# ToF_sensors.net
KiCad netlist of a schematic drawn in Altium Designer
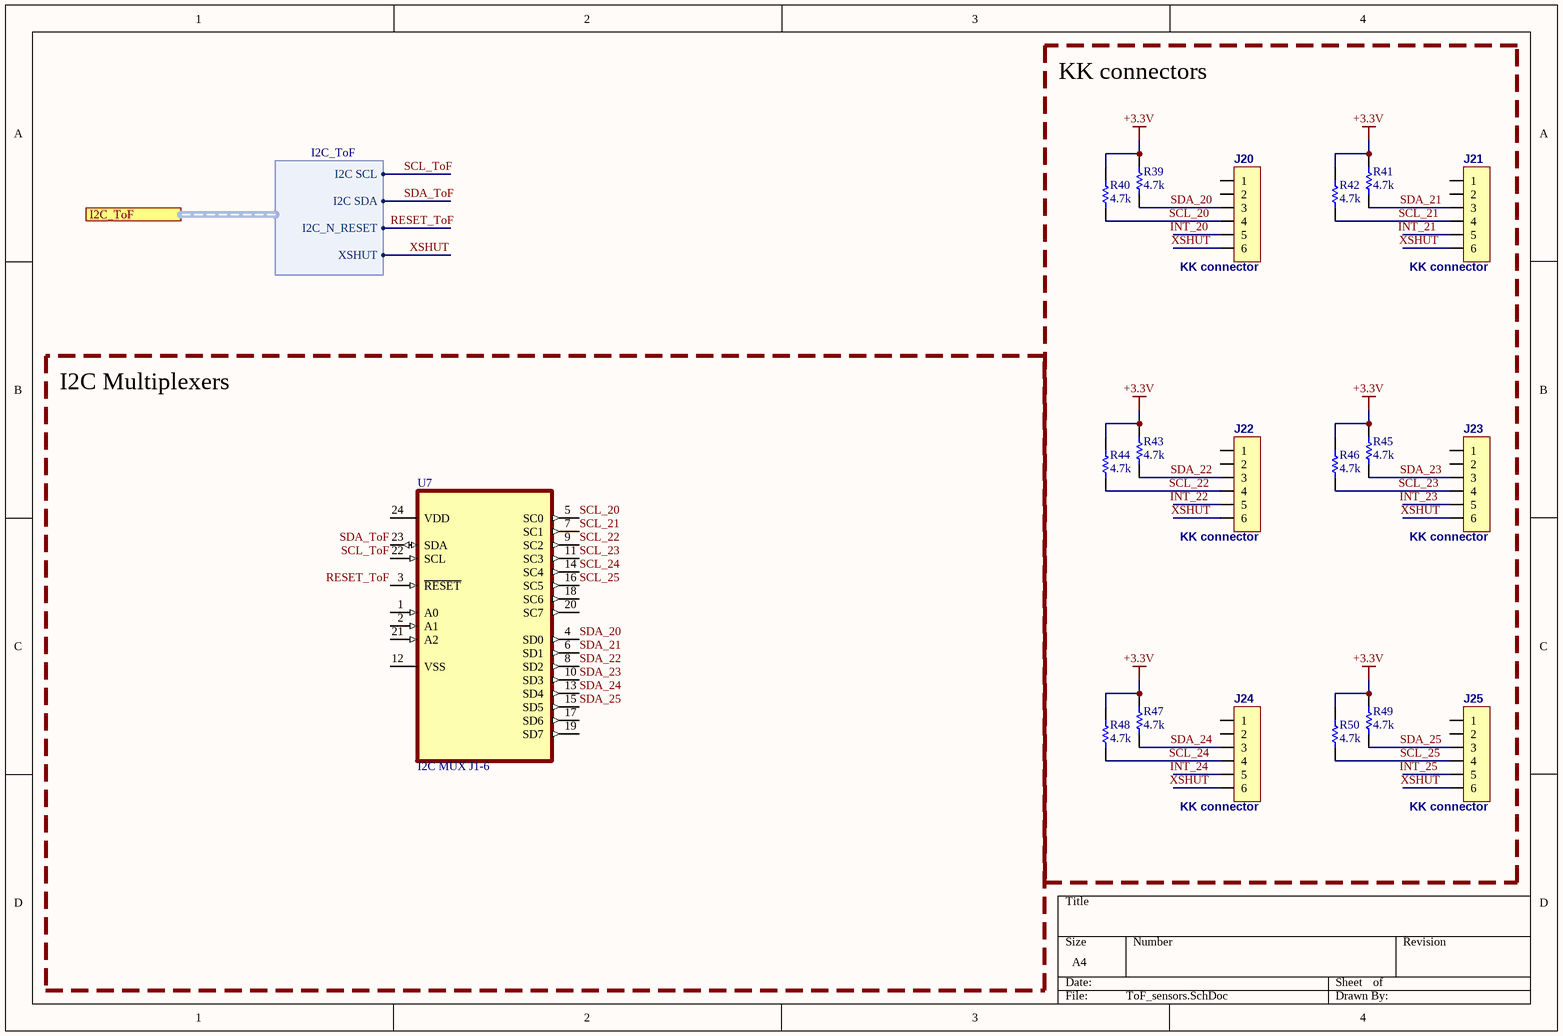
[diagram p0: ToF_sensors.SchDoc]

(export (version "E")
  (design (tool "Eeschema 10.0.6"))
  (components
    (comp (ref "J20")
      (value "KK connector")
      (footprint "KK/2.54/6")
      (description "Connector: PCB-cable; KK; socket; male; PIN:6; straight/right-angle; tinned; THT, KK/2,54mm")
      (libsource (lib "kk") (part "CN_6x1"))
    )
    (comp (ref "J21")
      (value "KK connector")
      (footprint "KK/2.54/6")
      (description "Connector: PCB-cable; KK; socket; male; PIN:6; straight/right-angle; tinned; THT, KK/2,54mm")
      (libsource (lib "kk") (part "CN_6x1"))
    )
    (comp (ref "J22")
      (value "KK connector")
      (footprint "KK/2.54/6")
      (description "Connector: PCB-cable; KK; socket; male; PIN:6; straight/right-angle; tinned; THT, KK/2,54mm")
      (libsource (lib "kk") (part "CN_6x1"))
    )
    (comp (ref "J23")
      (value "KK connector")
      (footprint "KK/2.54/6")
      (description "Connector: PCB-cable; KK; socket; male; PIN:6; straight/right-angle; tinned; THT, KK/2,54mm")
      (libsource (lib "kk") (part "CN_6x1"))
    )
    (comp (ref "J24")
      (value "KK connector")
      (footprint "KK/2.54/6")
      (description "Connector: PCB-cable; KK; socket; male; PIN:6; straight/right-angle; tinned; THT, KK/2,54mm")
      (libsource (lib "kk") (part "CN_6x1"))
    )
    (comp (ref "J25")
      (value "KK connector")
      (footprint "KK/2.54/6")
      (description "Connector: PCB-cable; KK; socket; male; PIN:6; straight/right-angle; tinned; THT, KK/2,54mm")
      (libsource (lib "kk") (part "CN_6x1"))
    )
    (comp (ref "R39")
      (value "4.7k")
      (footprint "RESC1609X50X30ML10T20")
      (description "RES 4,7K OHM 1% 0,1W 0603 RNCS0603BKE10K0")
      (fields (field (name "PART NUMBER") "CRCW060311K0FKEA") (field (name "MANUFACTURER") "Vishay Dale"))
      (libsource (lib "Altium Content Vault") (part "RES"))
    )
    (comp (ref "R40")
      (value "4.7k")
      (footprint "RESC1609X50X30ML10T20")
      (description "RES 4,7K OHM 1% 0,1W 0603 RNCS0603BKE10K0")
      (fields (field (name "PART NUMBER") "CRCW060311K0FKEA") (field (name "MANUFACTURER") "Vishay Dale"))
      (libsource (lib "Altium Content Vault") (part "RES"))
    )
    (comp (ref "R41")
      (value "4.7k")
      (footprint "RESC1609X50X30ML10T20")
      (description "RES 4,7K OHM 1% 0,1W 0603 RNCS0603BKE10K0")
      (fields (field (name "PART NUMBER") "CRCW060311K0FKEA") (field (name "MANUFACTURER") "Vishay Dale"))
      (libsource (lib "Altium Content Vault") (part "RES"))
    )
    (comp (ref "R42")
      (value "4.7k")
      (footprint "RESC1609X50X30ML10T20")
      (description "RES 4,7K OHM 1% 0,1W 0603 RNCS0603BKE10K0")
      (fields (field (name "PART NUMBER") "CRCW060311K0FKEA") (field (name "MANUFACTURER") "Vishay Dale"))
      (libsource (lib "Altium Content Vault") (part "RES"))
    )
    (comp (ref "R43")
      (value "4.7k")
      (footprint "RESC1609X50X30ML10T20")
      (description "RES 4,7K OHM 1% 0,1W 0603 RNCS0603BKE10K0")
      (fields (field (name "PART NUMBER") "CRCW060311K0FKEA") (field (name "MANUFACTURER") "Vishay Dale"))
      (libsource (lib "Altium Content Vault") (part "RES"))
    )
    (comp (ref "R44")
      (value "4.7k")
      (footprint "RESC1609X50X30ML10T20")
      (description "RES 4,7K OHM 1% 0,1W 0603 RNCS0603BKE10K0")
      (fields (field (name "PART NUMBER") "CRCW060311K0FKEA") (field (name "MANUFACTURER") "Vishay Dale"))
      (libsource (lib "Altium Content Vault") (part "RES"))
    )
    (comp (ref "R45")
      (value "4.7k")
      (footprint "RESC1609X50X30ML10T20")
      (description "RES 4,7K OHM 1% 0,1W 0603 RNCS0603BKE10K0")
      (fields (field (name "PART NUMBER") "CRCW060311K0FKEA") (field (name "MANUFACTURER") "Vishay Dale"))
      (libsource (lib "Altium Content Vault") (part "RES"))
    )
    (comp (ref "R46")
      (value "4.7k")
      (footprint "RESC1609X50X30ML10T20")
      (description "RES 4,7K OHM 1% 0,1W 0603 RNCS0603BKE10K0")
      (fields (field (name "PART NUMBER") "CRCW060311K0FKEA") (field (name "MANUFACTURER") "Vishay Dale"))
      (libsource (lib "Altium Content Vault") (part "RES"))
    )
    (comp (ref "R47")
      (value "4.7k")
      (footprint "RESC1609X50X30ML10T20")
      (description "RES 4,7K OHM 1% 0,1W 0603 RNCS0603BKE10K0")
      (fields (field (name "PART NUMBER") "CRCW060311K0FKEA") (field (name "MANUFACTURER") "Vishay Dale"))
      (libsource (lib "Altium Content Vault") (part "RES"))
    )
    (comp (ref "R48")
      (value "4.7k")
      (footprint "RESC1609X50X30ML10T20")
      (description "RES 4,7K OHM 1% 0,1W 0603 RNCS0603BKE10K0")
      (fields (field (name "PART NUMBER") "CRCW060311K0FKEA") (field (name "MANUFACTURER") "Vishay Dale"))
      (libsource (lib "Altium Content Vault") (part "RES"))
    )
    (comp (ref "R49")
      (value "4.7k")
      (footprint "RESC1609X50X30ML10T20")
      (description "RES 4,7K OHM 1% 0,1W 0603 RNCS0603BKE10K0")
      (fields (field (name "PART NUMBER") "CRCW060311K0FKEA") (field (name "MANUFACTURER") "Vishay Dale"))
      (libsource (lib "Altium Content Vault") (part "RES"))
    )
    (comp (ref "R50")
      (value "4.7k")
      (footprint "RESC1609X50X30ML10T20")
      (description "RES 4,7K OHM 1% 0,1W 0603 RNCS0603BKE10K0")
      (fields (field (name "PART NUMBER") "CRCW060311K0FKEA") (field (name "MANUFACTURER") "Vishay Dale"))
      (libsource (lib "Altium Content Vault") (part "RES"))
    )
    (comp (ref "U7")
      (value "I2C MUX J1-6")
      (footprint "SOP65P640X110-24N")
      (description "Translating Multiplexer Interface 24-TSSOP PCA9547PW,118")
      (fields (field (name "MP") "PCA9547PW,118") (field (name "MF") "NXP USA"))
      (libsource (lib "MyWorkspace") (part "PCA9547PW,118"))
    )
  )
  (nets
    (net (code "2") (name "+3.3V") (class "Default")
      (node (ref "R39") (pin "2") (pinfunction "2_2") (pintype "passive"))
      (node (ref "R40") (pin "2") (pinfunction "2_2") (pintype "passive"))
      (node (ref "R41") (pin "2") (pinfunction "2_2") (pintype "passive"))
      (node (ref "R42") (pin "2") (pinfunction "2_2") (pintype "passive"))
      (node (ref "R43") (pin "2") (pinfunction "2_2") (pintype "passive"))
      (node (ref "R44") (pin "2") (pinfunction "2_2") (pintype "passive"))
      (node (ref "R45") (pin "2") (pinfunction "2_2") (pintype "passive"))
      (node (ref "R46") (pin "2") (pinfunction "2_2") (pintype "passive"))
      (node (ref "R47") (pin "2") (pinfunction "2_2") (pintype "passive"))
      (node (ref "R48") (pin "2") (pinfunction "2_2") (pintype "passive"))
      (node (ref "R49") (pin "2") (pinfunction "2_2") (pintype "passive"))
      (node (ref "R50") (pin "2") (pinfunction "2_2") (pintype "passive"))
    )
    (net (code "3") (name "/INT_20") (class "Default")
      (node (ref "J20") (pin "5") (pinfunction "5_5") (pintype "passive"))
    )
    (net (code "4") (name "/INT_21") (class "Default")
      (node (ref "J21") (pin "5") (pinfunction "5_5") (pintype "passive"))
    )
    (net (code "5") (name "/INT_22") (class "Default")
      (node (ref "J22") (pin "5") (pinfunction "5_5") (pintype "passive"))
    )
    (net (code "6") (name "/INT_23") (class "Default")
      (node (ref "J23") (pin "5") (pinfunction "5_5") (pintype "passive"))
    )
    (net (code "7") (name "/INT_24") (class "Default")
      (node (ref "J24") (pin "5") (pinfunction "5_5") (pintype "passive"))
    )
    (net (code "8") (name "/INT_25") (class "Default")
      (node (ref "J25") (pin "5") (pinfunction "5_5") (pintype "passive"))
    )
    (net (code "9") (name "/RESET_ToF") (class "Default")
      (node (ref "U7") (pin "3") (pinfunction "~{RESET}_3") (pintype "input"))
    )
    (net (code "10") (name "/SCL_20") (class "Default")
      (node (ref "J20") (pin "4") (pinfunction "4_4") (pintype "passive"))
      (node (ref "R40") (pin "1") (pinfunction "1_1") (pintype "passive"))
      (node (ref "U7") (pin "5") (pinfunction "SC0_5") (pintype "output"))
    )
    (net (code "11") (name "/SCL_21") (class "Default")
      (node (ref "J21") (pin "4") (pinfunction "4_4") (pintype "passive"))
      (node (ref "R42") (pin "1") (pinfunction "1_1") (pintype "passive"))
      (node (ref "U7") (pin "7") (pinfunction "SC1_7") (pintype "output"))
    )
    (net (code "12") (name "/SCL_22") (class "Default")
      (node (ref "J22") (pin "4") (pinfunction "4_4") (pintype "passive"))
      (node (ref "R44") (pin "1") (pinfunction "1_1") (pintype "passive"))
      (node (ref "U7") (pin "9") (pinfunction "SC2_9") (pintype "output"))
    )
    (net (code "13") (name "/SCL_23") (class "Default")
      (node (ref "J23") (pin "4") (pinfunction "4_4") (pintype "passive"))
      (node (ref "R46") (pin "1") (pinfunction "1_1") (pintype "passive"))
      (node (ref "U7") (pin "11") (pinfunction "SC3_11") (pintype "output"))
    )
    (net (code "14") (name "/SCL_24") (class "Default")
      (node (ref "J24") (pin "4") (pinfunction "4_4") (pintype "passive"))
      (node (ref "R48") (pin "1") (pinfunction "1_1") (pintype "passive"))
      (node (ref "U7") (pin "14") (pinfunction "SC4_14") (pintype "output"))
    )
    (net (code "15") (name "/SCL_25") (class "Default")
      (node (ref "J25") (pin "4") (pinfunction "4_4") (pintype "passive"))
      (node (ref "R50") (pin "1") (pinfunction "1_1") (pintype "passive"))
      (node (ref "U7") (pin "16") (pinfunction "SC5_16") (pintype "output"))
    )
    (net (code "16") (name "/SCL_ToF") (class "Default")
      (node (ref "U7") (pin "22") (pinfunction "SCL_22") (pintype "input"))
    )
    (net (code "17") (name "/SDA_20") (class "Default")
      (node (ref "J20") (pin "3") (pinfunction "3_3") (pintype "passive"))
      (node (ref "R39") (pin "1") (pinfunction "1_1") (pintype "passive"))
      (node (ref "U7") (pin "4") (pinfunction "SD0_4") (pintype "output"))
    )
    (net (code "18") (name "/SDA_21") (class "Default")
      (node (ref "J21") (pin "3") (pinfunction "3_3") (pintype "passive"))
      (node (ref "R41") (pin "1") (pinfunction "1_1") (pintype "passive"))
      (node (ref "U7") (pin "6") (pinfunction "SD1_6") (pintype "output"))
    )
    (net (code "19") (name "/SDA_22") (class "Default")
      (node (ref "J22") (pin "3") (pinfunction "3_3") (pintype "passive"))
      (node (ref "R43") (pin "1") (pinfunction "1_1") (pintype "passive"))
      (node (ref "U7") (pin "8") (pinfunction "SD2_8") (pintype "output"))
    )
    (net (code "20") (name "/SDA_23") (class "Default")
      (node (ref "J23") (pin "3") (pinfunction "3_3") (pintype "passive"))
      (node (ref "R45") (pin "1") (pinfunction "1_1") (pintype "passive"))
      (node (ref "U7") (pin "10") (pinfunction "SD3_10") (pintype "output"))
    )
    (net (code "21") (name "/SDA_24") (class "Default")
      (node (ref "J24") (pin "3") (pinfunction "3_3") (pintype "passive"))
      (node (ref "R47") (pin "1") (pinfunction "1_1") (pintype "passive"))
      (node (ref "U7") (pin "13") (pinfunction "SD4_13") (pintype "output"))
    )
    (net (code "22") (name "/SDA_25") (class "Default")
      (node (ref "J25") (pin "3") (pinfunction "3_3") (pintype "passive"))
      (node (ref "R49") (pin "1") (pinfunction "1_1") (pintype "passive"))
      (node (ref "U7") (pin "15") (pinfunction "SD5_15") (pintype "output"))
    )
    (net (code "23") (name "/SDA_ToF") (class "Default")
      (node (ref "U7") (pin "23") (pinfunction "SDA_23") (pintype "bidirectional"))
    )
    (net (code "24") (name "/XSHUT") (class "Default")
      (node (ref "J20") (pin "6") (pinfunction "6_6") (pintype "passive"))
      (node (ref "J21") (pin "6") (pinfunction "6_6") (pintype "passive"))
      (node (ref "J22") (pin "6") (pinfunction "6_6") (pintype "passive"))
      (node (ref "J23") (pin "6") (pinfunction "6_6") (pintype "passive"))
      (node (ref "J24") (pin "6") (pinfunction "6_6") (pintype "passive"))
      (node (ref "J25") (pin "6") (pinfunction "6_6") (pintype "passive"))
    )
    (net (code "26") (name "unconnected-(J20-Pad1)") (class "Default")
      (node (ref "J20") (pin "1") (pinfunction "1_1") (pintype "passive"))
    )
    (net (code "27") (name "unconnected-(J20-Pad2)") (class "Default")
      (node (ref "J20") (pin "2") (pinfunction "2_2") (pintype "passive"))
    )
    (net (code "28") (name "unconnected-(J21-Pad1)") (class "Default")
      (node (ref "J21") (pin "1") (pinfunction "1_1") (pintype "passive"))
    )
    (net (code "29") (name "unconnected-(J21-Pad2)") (class "Default")
      (node (ref "J21") (pin "2") (pinfunction "2_2") (pintype "passive"))
    )
    (net (code "30") (name "unconnected-(J22-Pad1)") (class "Default")
      (node (ref "J22") (pin "1") (pinfunction "1_1") (pintype "passive"))
    )
    (net (code "31") (name "unconnected-(J22-Pad2)") (class "Default")
      (node (ref "J22") (pin "2") (pinfunction "2_2") (pintype "passive"))
    )
    (net (code "32") (name "unconnected-(J23-Pad1)") (class "Default")
      (node (ref "J23") (pin "1") (pinfunction "1_1") (pintype "passive"))
    )
    (net (code "33") (name "unconnected-(J23-Pad2)") (class "Default")
      (node (ref "J23") (pin "2") (pinfunction "2_2") (pintype "passive"))
    )
    (net (code "34") (name "unconnected-(J24-Pad1)") (class "Default")
      (node (ref "J24") (pin "1") (pinfunction "1_1") (pintype "passive"))
    )
    (net (code "35") (name "unconnected-(J24-Pad2)") (class "Default")
      (node (ref "J24") (pin "2") (pinfunction "2_2") (pintype "passive"))
    )
    (net (code "36") (name "unconnected-(J25-Pad1)") (class "Default")
      (node (ref "J25") (pin "1") (pinfunction "1_1") (pintype "passive"))
    )
    (net (code "37") (name "unconnected-(J25-Pad2)") (class "Default")
      (node (ref "J25") (pin "2") (pinfunction "2_2") (pintype "passive"))
    )
    (net (code "38") (name "unconnected-(U7-A0-Pad1)") (class "Default")
      (node (ref "U7") (pin "1") (pinfunction "A0_1") (pintype "input"))
    )
    (net (code "39") (name "unconnected-(U7-A1-Pad2)") (class "Default")
      (node (ref "U7") (pin "2") (pinfunction "A1_2") (pintype "input"))
    )
    (net (code "40") (name "unconnected-(U7-A2-Pad21)") (class "Default")
      (node (ref "U7") (pin "21") (pinfunction "A2_21") (pintype "input"))
    )
    (net (code "41") (name "unconnected-(U7-SC6-Pad18)") (class "Default")
      (node (ref "U7") (pin "18") (pinfunction "SC6_18") (pintype "output"))
    )
    (net (code "42") (name "unconnected-(U7-SC7-Pad20)") (class "Default")
      (node (ref "U7") (pin "20") (pinfunction "SC7_20") (pintype "output"))
    )
    (net (code "43") (name "unconnected-(U7-SD6-Pad17)") (class "Default")
      (node (ref "U7") (pin "17") (pinfunction "SD6_17") (pintype "output"))
    )
    (net (code "44") (name "unconnected-(U7-SD7-Pad19)") (class "Default")
      (node (ref "U7") (pin "19") (pinfunction "SD7_19") (pintype "output"))
    )
    (net (code "45") (name "unconnected-(U7-VDD-Pad24)") (class "Default")
      (node (ref "U7") (pin "24") (pinfunction "VDD_24") (pintype "power_in"))
    )
    (net (code "46") (name "unconnected-(U7-VSS-Pad12)") (class "Default")
      (node (ref "U7") (pin "12") (pinfunction "VSS_12") (pintype "passive"))
    )
  )
)
